# CT_switching.net
KiCad netlist of a schematic drawn in Altium Designer
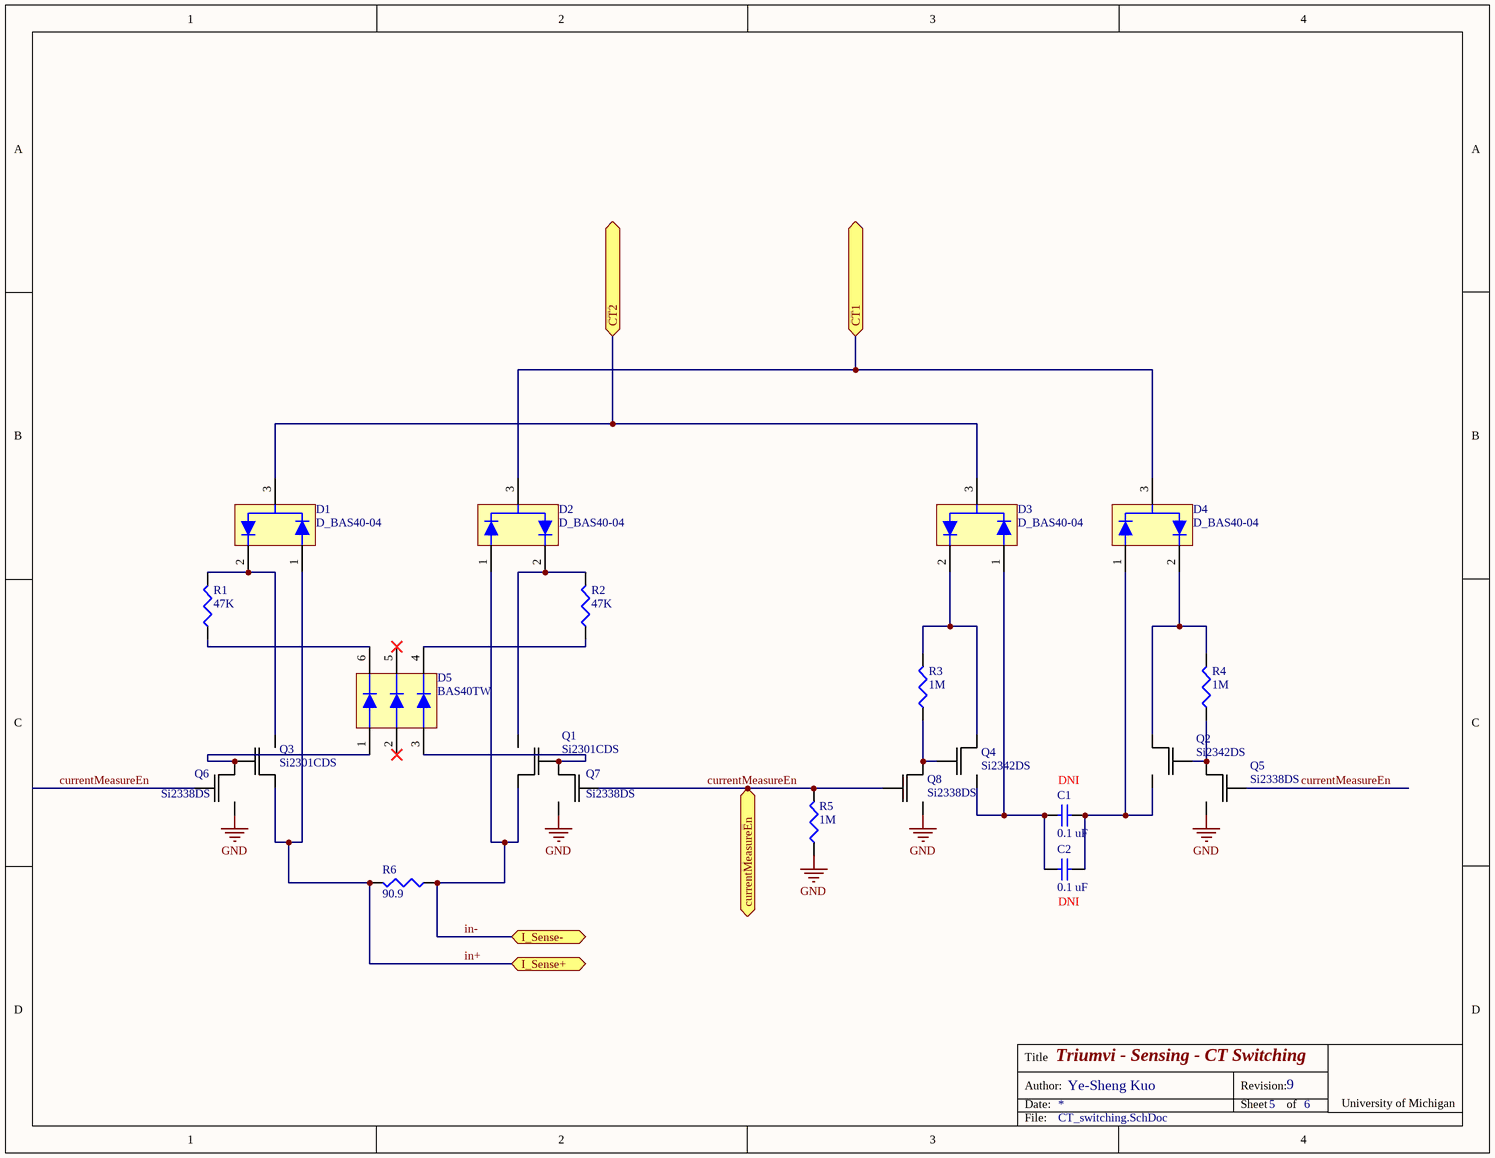
[diagram p0: CT_switching.SchDoc]

(export (version "E")
  (design (tool "Eeschema 10.0.6"))
  (components
    (comp (ref "C1")
      (value "0.1 uF")
      (footprint "0603")
      (description "Ceramic capacitor, 0.1 uF, 0603 package")
      (fields (field (name "TOLERANCE") "10%") (field (name "Comment") "Ceramic capacitor"))
      (libsource (lib "rlc") (part "C_0.1u_25V_0603_ceramic"))
    )
    (comp (ref "C2")
      (value "0.1 uF")
      (footprint "0603")
      (description "Ceramic capacitor, 0.1 uF, 0603 package")
      (fields (field (name "TOLERANCE") "10%") (field (name "Comment") "Ceramic capacitor"))
      (libsource (lib "rlc") (part "C_0.1u_25V_0603_ceramic"))
    )
    (comp (ref "D1")
      (value "D_BAS40-04")
      (footprint "SOT23-3")
      (description "SURFACE MOUNT SCHOTTKY BARRIER DIODE")
      (libsource (lib "") (part "D_BAS40-04_1"))
    )
    (comp (ref "D2")
      (value "D_BAS40-04")
      (footprint "SOT23-3")
      (description "SURFACE MOUNT SCHOTTKY BARRIER DIODE")
      (libsource (lib "rlc") (part "D_BAS40-04"))
    )
    (comp (ref "D3")
      (value "D_BAS40-04")
      (footprint "SOT23-3")
      (description "SURFACE MOUNT SCHOTTKY BARRIER DIODE")
      (libsource (lib "") (part "D_BAS40-04_1"))
    )
    (comp (ref "D4")
      (value "D_BAS40-04")
      (footprint "SOT23-3")
      (description "SURFACE MOUNT SCHOTTKY BARRIER DIODE")
      (libsource (lib "rlc") (part "D_BAS40-04"))
    )
    (comp (ref "D5")
      (value "BAS40TW")
      (footprint "SOT-363")
      (description "SURFACE MOUNT SCHOTTKY BARRIER DIODE ARRAYS")
      (libsource (lib "rlc") (part "D_BAS40TW"))
    )
    (comp (ref "Q1")
      (value "Si2301CDS")
      (footprint "SOT23-3")
      (description "P-Channel 20 V (D-S) MOSFET")
      (libsource (lib "transistors") (part "Si2301CDS"))
    )
    (comp (ref "Q2")
      (value "Si2342DS")
      (footprint "SOT23-3")
      (description "N-Channel 8 V (D-S) MOSFET")
      (libsource (lib "transistors") (part "Si2342DS"))
    )
    (comp (ref "Q3")
      (value "Si2301CDS")
      (footprint "SOT23-3")
      (description "P-Channel 20 V (D-S) MOSFET")
      (libsource (lib "transistors") (part "Si2301CDS"))
    )
    (comp (ref "Q4")
      (value "Si2342DS")
      (footprint "SOT23-3")
      (description "N-Channel 8 V (D-S) MOSFET")
      (libsource (lib "transistors") (part "Si2342DS"))
    )
    (comp (ref "Q5")
      (value "Si2338DS")
      (footprint "SOT23-3")
      (description "N-Channel 30 V (D-S) MOSFET")
      (libsource (lib "transistors") (part "Si2338DS"))
    )
    (comp (ref "Q6")
      (value "Si2338DS")
      (footprint "SOT23-3")
      (description "N-Channel 30 V (D-S) MOSFET")
      (libsource (lib "transistors") (part "Si2338DS"))
    )
    (comp (ref "Q7")
      (value "Si2338DS")
      (footprint "SOT23-3")
      (description "N-Channel 30 V (D-S) MOSFET")
      (libsource (lib "transistors") (part "Si2338DS"))
    )
    (comp (ref "Q8")
      (value "Si2338DS")
      (footprint "SOT23-3")
      (description "N-Channel 30 V (D-S) MOSFET")
      (libsource (lib "transistors") (part "Si2338DS"))
    )
    (comp (ref "R1")
      (value "47K")
      (footprint "0402")
      (description "Chip resistor, 47K, 0402 package")
      (fields (field (name "TOLERANCE") "1%") (field (name "POWER") "1/16 W"))
      (libsource (lib "rlc") (part "R_47K_0402"))
    )
    (comp (ref "R2")
      (value "47K")
      (footprint "0402")
      (description "Chip resistor, 47K, 0402 package")
      (fields (field (name "TOLERANCE") "1%") (field (name "POWER") "1/16 W"))
      (libsource (lib "rlc") (part "R_47K_0402"))
    )
    (comp (ref "R3")
      (value "1M")
      (footprint "0402")
      (description "Chip resistor, 1M, 0402 package")
      (fields (field (name "TOLERANCE") "1%") (field (name "POWER") "1/16 W"))
      (libsource (lib "rlc") (part "R_1M_0402"))
    )
    (comp (ref "R4")
      (value "1M")
      (footprint "0402")
      (description "Chip resistor, 1M, 0402 package")
      (fields (field (name "TOLERANCE") "1%") (field (name "POWER") "1/16 W"))
      (libsource (lib "rlc") (part "R_1M_0402"))
    )
    (comp (ref "R5")
      (value "1M")
      (footprint "0402")
      (description "Chip resistor, 1M, 0402 package")
      (fields (field (name "TOLERANCE") "1%") (field (name "POWER") "1/16 W"))
      (libsource (lib "rlc") (part "R_1M_0402"))
    )
    (comp (ref "R6")
      (value "90.9")
      (footprint "0603")
      (description "Chip resistor, 90.9, 0603 package")
      (fields (field (name "TOLERANCE") "0.1%") (field (name "POWER") "1/10 W"))
      (libsource (lib "rlc") (part "R_90.9_0603"))
    )
  )
  (nets
    (net (code "1") (name "/CT1") (class "Default")
      (node (ref "D2") (pin "3") (pinfunction "3_3") (pintype "passive"))
      (node (ref "D4") (pin "3") (pinfunction "3_3") (pintype "passive"))
    )
    (net (code "2") (name "/CT2") (class "Default")
      (node (ref "D1") (pin "3") (pinfunction "3_3") (pintype "passive"))
      (node (ref "D3") (pin "3") (pinfunction "3_3") (pintype "passive"))
    )
    (net (code "3") (name "/currentMeasureEn") (class "Default")
      (node (ref "Q5") (pin "1") (pinfunction "G_1") (pintype "passive"))
      (node (ref "Q6") (pin "1") (pinfunction "G_1") (pintype "passive"))
      (node (ref "Q7") (pin "1") (pinfunction "G_1") (pintype "passive"))
      (node (ref "Q8") (pin "1") (pinfunction "G_1") (pintype "passive"))
      (node (ref "R5") (pin "1") (pintype "passive"))
    )
    (net (code "4") (name "/in+") (class "Default")
      (node (ref "D1") (pin "1") (pinfunction "1_1") (pintype "passive"))
      (node (ref "Q3") (pin "3") (pinfunction "D_3") (pintype "passive"))
      (node (ref "R6") (pin "1") (pintype "passive"))
    )
    (net (code "5") (name "/in-") (class "Default")
      (node (ref "D2") (pin "1") (pinfunction "1_1") (pintype "passive"))
      (node (ref "Q1") (pin "3") (pinfunction "D_3") (pintype "passive"))
      (node (ref "R6") (pin "2") (pintype "passive"))
    )
    (net (code "6") (name "GND") (class "Default")
      (node (ref "Q5") (pin "2") (pinfunction "S_2") (pintype "passive"))
      (node (ref "Q6") (pin "2") (pinfunction "S_2") (pintype "passive"))
      (node (ref "Q7") (pin "2") (pinfunction "S_2") (pintype "passive"))
      (node (ref "Q8") (pin "2") (pinfunction "S_2") (pintype "passive"))
      (node (ref "R5") (pin "2") (pintype "passive"))
    )
    (net (code "7") (name "Net-(D5-Pad4)") (class "Default")
      (node (ref "D5") (pin "4") (pinfunction "4_4") (pintype "passive"))
      (node (ref "R2") (pin "2") (pintype "passive"))
    )
    (net (code "8") (name "Net-(D5-Pad6)") (class "Default")
      (node (ref "D5") (pin "6") (pinfunction "6_6") (pintype "passive"))
      (node (ref "R1") (pin "2") (pintype "passive"))
    )
    (net (code "9") (name "Net-(Q1-G)") (class "Default")
      (node (ref "D5") (pin "3") (pinfunction "3_3") (pintype "passive"))
      (node (ref "Q1") (pin "1") (pinfunction "G_1") (pintype "passive"))
      (node (ref "Q7") (pin "3") (pinfunction "D_3") (pintype "passive"))
    )
    (net (code "10") (name "Net-(Q1-S)") (class "Default")
      (node (ref "D2") (pin "2") (pinfunction "2_2") (pintype "passive"))
      (node (ref "Q1") (pin "2") (pinfunction "S_2") (pintype "passive"))
      (node (ref "R2") (pin "1") (pintype "passive"))
    )
    (net (code "11") (name "Net-(Q2-D)") (class "Default")
      (node (ref "D4") (pin "2") (pinfunction "2_2") (pintype "passive"))
      (node (ref "Q2") (pin "3") (pinfunction "D_3") (pintype "passive"))
      (node (ref "R4") (pin "1") (pintype "passive"))
    )
    (net (code "12") (name "Net-(Q2-G)") (class "Default")
      (node (ref "Q2") (pin "1") (pinfunction "G_1") (pintype "passive"))
      (node (ref "Q5") (pin "3") (pinfunction "D_3") (pintype "passive"))
      (node (ref "R4") (pin "2") (pintype "passive"))
    )
    (net (code "13") (name "Net-(Q2-S)") (class "Default")
      (node (ref "C1") (pin "2") (pintype "passive"))
      (node (ref "C2") (pin "2") (pintype "passive"))
      (node (ref "D4") (pin "1") (pinfunction "1_1") (pintype "passive"))
      (node (ref "Q2") (pin "2") (pinfunction "S_2") (pintype "passive"))
    )
    (net (code "14") (name "Net-(Q3-G)") (class "Default")
      (node (ref "D5") (pin "1") (pinfunction "1_1") (pintype "passive"))
      (node (ref "Q3") (pin "1") (pinfunction "G_1") (pintype "passive"))
      (node (ref "Q6") (pin "3") (pinfunction "D_3") (pintype "passive"))
    )
    (net (code "15") (name "Net-(Q3-S)") (class "Default")
      (node (ref "D1") (pin "2") (pinfunction "2_2") (pintype "passive"))
      (node (ref "Q3") (pin "2") (pinfunction "S_2") (pintype "passive"))
      (node (ref "R1") (pin "1") (pintype "passive"))
    )
    (net (code "16") (name "Net-(Q4-D)") (class "Default")
      (node (ref "D3") (pin "2") (pinfunction "2_2") (pintype "passive"))
      (node (ref "Q4") (pin "3") (pinfunction "D_3") (pintype "passive"))
      (node (ref "R3") (pin "1") (pintype "passive"))
    )
    (net (code "17") (name "Net-(Q4-G)") (class "Default")
      (node (ref "Q4") (pin "1") (pinfunction "G_1") (pintype "passive"))
      (node (ref "Q8") (pin "3") (pinfunction "D_3") (pintype "passive"))
      (node (ref "R3") (pin "2") (pintype "passive"))
    )
    (net (code "18") (name "Net-(Q4-S)") (class "Default")
      (node (ref "C1") (pin "1") (pintype "passive"))
      (node (ref "C2") (pin "1") (pintype "passive"))
      (node (ref "D3") (pin "1") (pinfunction "1_1") (pintype "passive"))
      (node (ref "Q4") (pin "2") (pinfunction "S_2") (pintype "passive"))
    )
    (net (code "19") (name "unconnected-(D5-Pad2)") (class "Default")
      (node (ref "D5") (pin "2") (pinfunction "2_2") (pintype "passive+no_connect"))
    )
    (net (code "20") (name "unconnected-(D5-Pad5)") (class "Default")
      (node (ref "D5") (pin "5") (pinfunction "5_5") (pintype "passive+no_connect"))
    )
  )
)
